# Hydrometer.net
KiCad netlist of a schematic drawn in EAGLE
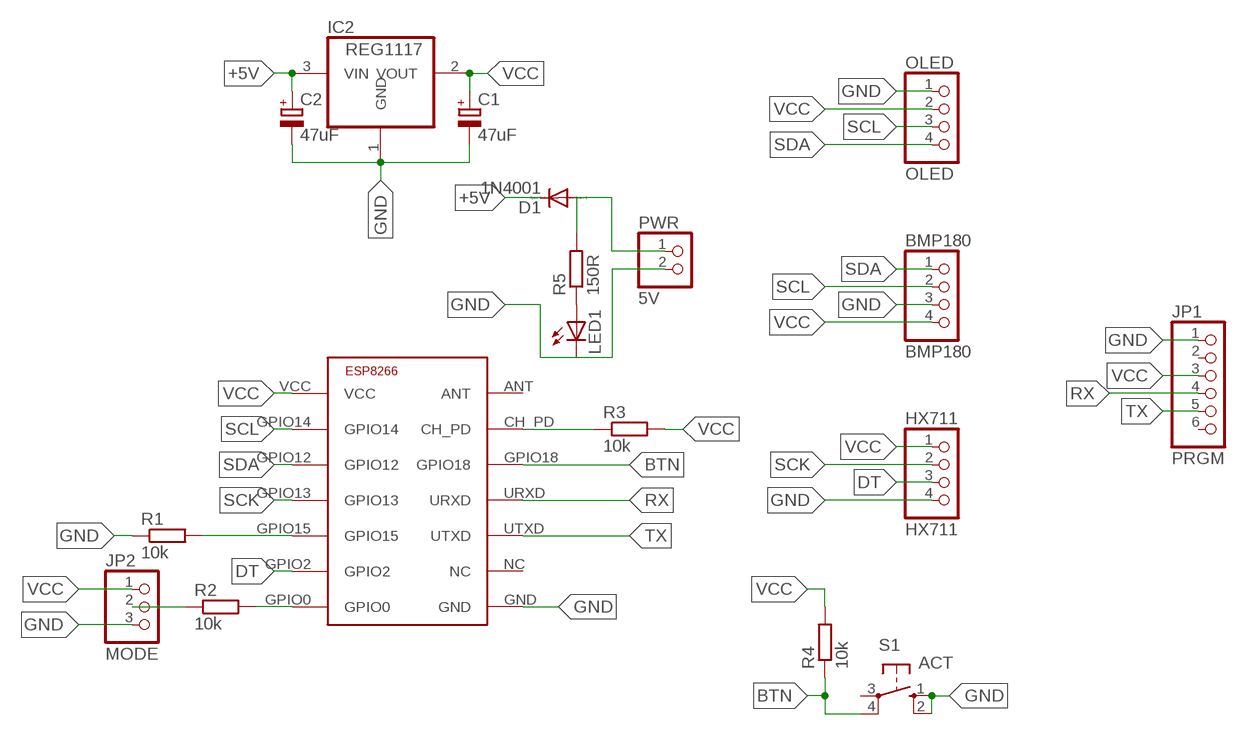
[diagram p0: schematic, sheet 1]

(export (version "E")
  (design (tool "Eeschema 10.0.6"))
  (components
    (comp (ref "BMP180")
      (value "BMP180")
      (footprint "eagle-import:1X04")
      (libsource (lib "eagle-import") (part "PINHD-1X4"))
    )
    (comp (ref "C1")
      (value "47uF")
      (footprint "eagle-import:E2-5")
      (libsource (lib "eagle-import") (part "CPOL-EUE2-5"))
    )
    (comp (ref "C2")
      (value "47uF")
      (footprint "eagle-import:E2,5-5")
      (libsource (lib "eagle-import") (part "CPOL-EUE2.5-5"))
    )
    (comp (ref "D1")
      (value "1N4001")
      (footprint "eagle-import:DO41-10")
      (libsource (lib "eagle-import") (part "1N4004"))
    )
    (comp (ref "HX711")
      (value "HX711")
      (footprint "eagle-import:1X04")
      (libsource (lib "eagle-import") (part "PINHD-1X4"))
    )
    (comp (ref "IC2")
      (value "REG1117")
      (footprint "eagle-import:SOT223")
      (libsource (lib "eagle-import") (part "REG1117"))
    )
    (comp (ref "JP1")
      (value "PRGM")
      (footprint "eagle-import:1X06")
      (libsource (lib "eagle-import") (part "PINHD-1X6"))
    )
    (comp (ref "JP2")
      (value "MODE")
      (footprint "eagle-import:1X03")
      (libsource (lib "eagle-import") (part "PINHD-1X3"))
    )
    (comp (ref "LED1")
      (value "LED3MM")
      (footprint "eagle-import:LED3MM")
      (libsource (lib "eagle-import") (part "LED3MM"))
    )
    (comp (ref "OLED")
      (value "OLED")
      (footprint "eagle-import:1X04")
      (libsource (lib "eagle-import") (part "PINHD-1X4"))
    )
    (comp (ref "PWR")
      (value "5V")
      (footprint "eagle-import:1X02")
      (libsource (lib "eagle-import") (part "PINHD-1X2"))
    )
    (comp (ref "R1")
      (value "10k")
      (footprint "eagle-import:R1206")
      (libsource (lib "eagle-import") (part "R-EU_R1206"))
    )
    (comp (ref "R2")
      (value "10k")
      (footprint "eagle-import:0204_7")
      (libsource (lib "eagle-import") (part "R-EU_0204/7"))
    )
    (comp (ref "R3")
      (value "10k")
      (footprint "eagle-import:R1206")
      (libsource (lib "eagle-import") (part "R-EU_R1206"))
    )
    (comp (ref "R4")
      (value "10k")
      (footprint "eagle-import:R1206")
      (libsource (lib "eagle-import") (part "R-EU_R1206"))
    )
    (comp (ref "R5")
      (value "150R")
      (footprint "eagle-import:0204_7")
      (libsource (lib "eagle-import") (part "R-EU_0204/7"))
    )
    (comp (ref "S1")
      (value "ACT")
      (footprint "eagle-import:B3F-10XX")
      (fields (field (name "MPN") "B3F-1000"))
      (libsource (lib "eagle-import") (part "10-XX"))
    )
    (comp (ref "U$1")
      (value "ESP8266-03")
      (footprint "eagle-import:ESP-03")
      (libsource (lib "eagle-import") (part "ESP8266-03"))
    )
  )
  (nets
    (net (code "1") (name "+5V") (class "Default")
      (node (ref "C2") (pin "+") (pinfunction "+_+") (pintype "passive"))
      (node (ref "D1") (pin "C") (pinfunction "C_C") (pintype "passive"))
      (node (ref "IC2") (pin "3") (pinfunction "VIN_3") (pintype "input"))
    )
    (net (code "2") (name "BTN") (class "Default")
      (node (ref "R4") (pin "1") (pinfunction "1_1") (pintype "passive"))
      (node (ref "S1") (pin "4") (pinfunction "P1_4") (pintype "passive"))
      (node (ref "U$1") (pin "GPIO18") (pinfunction "GPIO18_GPIO18") (pintype "bidirectional"))
    )
    (net (code "3") (name "DT") (class "Default")
      (node (ref "HX711") (pin "3") (pinfunction "3_3") (pintype "passive"))
      (node (ref "U$1") (pin "GPIO2") (pinfunction "GPIO2_GPIO2") (pintype "bidirectional"))
    )
    (net (code "4") (name "GND") (class "Default")
      (node (ref "BMP180") (pin "3") (pinfunction "3_3") (pintype "passive"))
      (node (ref "C1") (pin "-") (pinfunction "-_-") (pintype "passive"))
      (node (ref "C2") (pin "-") (pinfunction "-_-") (pintype "passive"))
      (node (ref "HX711") (pin "4") (pinfunction "4_4") (pintype "passive"))
      (node (ref "IC2") (pin "1") (pinfunction "GND_1") (pintype "power_in"))
      (node (ref "JP1") (pin "1") (pinfunction "1_1") (pintype "passive"))
      (node (ref "JP2") (pin "3") (pinfunction "3_3") (pintype "passive"))
      (node (ref "LED1") (pin "K") (pinfunction "C_K") (pintype "passive"))
      (node (ref "OLED") (pin "1") (pinfunction "1_1") (pintype "passive"))
      (node (ref "PWR") (pin "2") (pinfunction "2_2") (pintype "passive"))
      (node (ref "R1") (pin "1") (pinfunction "1_1") (pintype "passive"))
      (node (ref "S1") (pin "1") (pinfunction "S_1") (pintype "passive"))
      (node (ref "S1") (pin "2") (pinfunction "S1_2") (pintype "passive"))
      (node (ref "U$1") (pin "GND") (pinfunction "GND_GND") (pintype "bidirectional"))
    )
    (net (code "5") (name "Net-(D1-PadA)") (class "Default")
      (node (ref "D1") (pin "A") (pinfunction "A_A") (pintype "passive"))
      (node (ref "PWR") (pin "1") (pinfunction "1_1") (pintype "passive"))
      (node (ref "R5") (pin "2") (pinfunction "2_2") (pintype "passive"))
    )
    (net (code "6") (name "Net-(JP2-Pad2)") (class "Default")
      (node (ref "JP2") (pin "2") (pinfunction "2_2") (pintype "passive"))
      (node (ref "R2") (pin "1") (pinfunction "1_1") (pintype "passive"))
    )
    (net (code "7") (name "Net-(LED1-PadA)") (class "Default")
      (node (ref "LED1") (pin "A") (pinfunction "A_A") (pintype "passive"))
      (node (ref "R5") (pin "1") (pinfunction "1_1") (pintype "passive"))
    )
    (net (code "8") (name "Net-(R1-Pad2)") (class "Default")
      (node (ref "R1") (pin "2") (pinfunction "2_2") (pintype "passive"))
      (node (ref "U$1") (pin "GPIO15") (pinfunction "GPIO15_GPIO15") (pintype "bidirectional"))
    )
    (net (code "9") (name "Net-(R2-Pad2)") (class "Default")
      (node (ref "R2") (pin "2") (pinfunction "2_2") (pintype "passive"))
      (node (ref "U$1") (pin "GPIO0") (pinfunction "GPIO0_GPIO0") (pintype "bidirectional"))
    )
    (net (code "10") (name "Net-(R3-Pad1)") (class "Default")
      (node (ref "R3") (pin "1") (pinfunction "1_1") (pintype "passive"))
      (node (ref "U$1") (pin "CH_PD") (pinfunction "CH_PD_CH_PD") (pintype "bidirectional"))
    )
    (net (code "11") (name "RX") (class "Default")
      (node (ref "JP1") (pin "4") (pinfunction "4_4") (pintype "passive"))
      (node (ref "U$1") (pin "URXD") (pinfunction "URXD_URXD") (pintype "bidirectional"))
    )
    (net (code "12") (name "SCK") (class "Default")
      (node (ref "HX711") (pin "2") (pinfunction "2_2") (pintype "passive"))
      (node (ref "U$1") (pin "GPIO13") (pinfunction "GPIO13_GPIO13") (pintype "bidirectional"))
    )
    (net (code "13") (name "SCL") (class "Default")
      (node (ref "BMP180") (pin "2") (pinfunction "2_2") (pintype "passive"))
      (node (ref "OLED") (pin "3") (pinfunction "3_3") (pintype "passive"))
      (node (ref "U$1") (pin "GPIO14") (pinfunction "GPIO14_GPIO14") (pintype "bidirectional"))
    )
    (net (code "14") (name "SDA") (class "Default")
      (node (ref "BMP180") (pin "1") (pinfunction "1_1") (pintype "passive"))
      (node (ref "OLED") (pin "4") (pinfunction "4_4") (pintype "passive"))
      (node (ref "U$1") (pin "GPIO12") (pinfunction "GPIO12_GPIO12") (pintype "bidirectional"))
    )
    (net (code "15") (name "TX") (class "Default")
      (node (ref "JP1") (pin "5") (pinfunction "5_5") (pintype "passive"))
      (node (ref "U$1") (pin "UTXD") (pinfunction "UTXD_UTXD") (pintype "bidirectional"))
    )
    (net (code "16") (name "VCC") (class "Default")
      (node (ref "BMP180") (pin "4") (pinfunction "4_4") (pintype "passive"))
      (node (ref "C1") (pin "+") (pinfunction "+_+") (pintype "passive"))
      (node (ref "HX711") (pin "1") (pinfunction "1_1") (pintype "passive"))
      (node (ref "IC2") (pin "2") (pinfunction "VOUT_2") (pintype "output"))
      (node (ref "JP1") (pin "3") (pinfunction "3_3") (pintype "passive"))
      (node (ref "JP2") (pin "1") (pinfunction "1_1") (pintype "passive"))
      (node (ref "OLED") (pin "2") (pinfunction "2_2") (pintype "passive"))
      (node (ref "R3") (pin "2") (pinfunction "2_2") (pintype "passive"))
      (node (ref "R4") (pin "2") (pinfunction "2_2") (pintype "passive"))
      (node (ref "U$1") (pin "VCC") (pinfunction "VCC_VCC") (pintype "bidirectional"))
    )
    (net (code "17") (name "unconnected-(JP1-Pad2)") (class "Default")
      (node (ref "JP1") (pin "2") (pinfunction "2_2") (pintype "passive"))
    )
    (net (code "18") (name "unconnected-(JP1-Pad6)") (class "Default")
      (node (ref "JP1") (pin "6") (pinfunction "6_6") (pintype "passive"))
    )
    (net (code "19") (name "unconnected-(S1-P-Pad3)") (class "Default")
      (node (ref "S1") (pin "3") (pinfunction "P_3") (pintype "passive"))
    )
    (net (code "20") (name "unconnected-(U$1-PadANT)") (class "Default")
      (node (ref "U$1") (pin "ANT") (pinfunction "ANT_ANT") (pintype "bidirectional"))
    )
    (net (code "21") (name "unconnected-(U$1-PadNC)") (class "Default")
      (node (ref "U$1") (pin "NC") (pinfunction "NC_NC") (pintype "bidirectional"))
    )
  )
)
